# LIDO-HW_100_FrontConnector.net
KiCad netlist of a schematic drawn in Altium Designer
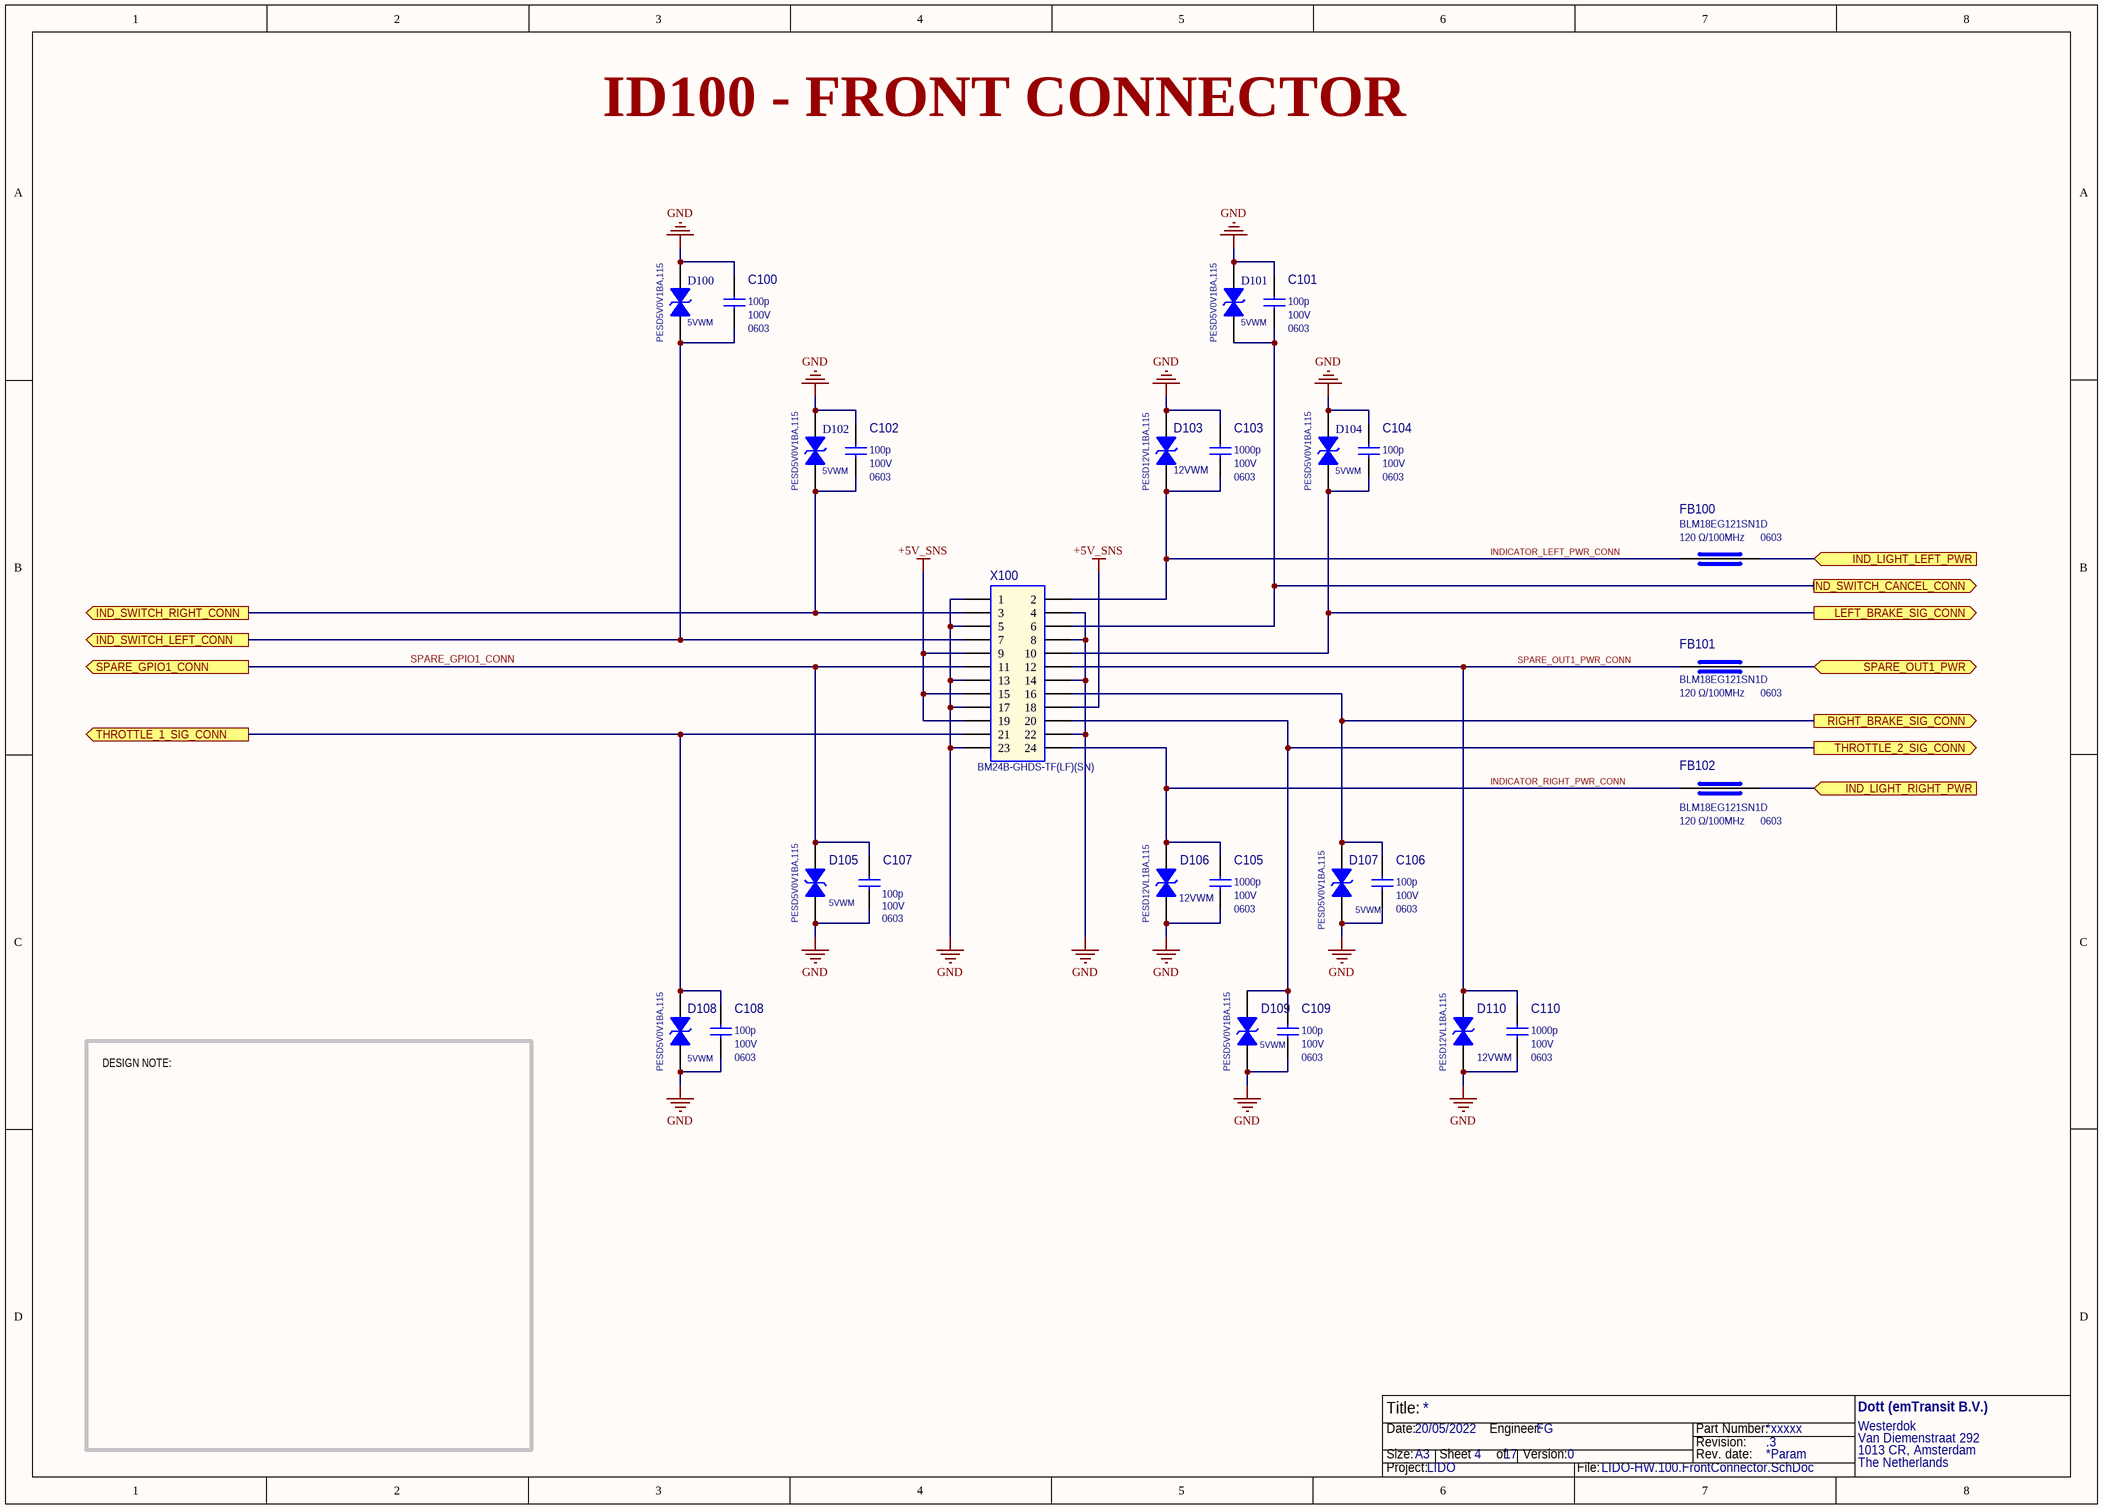
[diagram p0: LIDO-HW.100.FrontConnector.SchDoc]

(export (version "E")
  (design (tool "Eeschema 10.0.6"))
  (components
    (comp (ref "C100")
      (value "100p")
      (footprint "CAP_0603_1608X90-N_MURATA_A")
      (description "CAP CER 100PF 100V C0G 0603")
      (fields
        (field (name "MANUFACTURER PART NUMBER") "CGA3E2C0G2A101J080AA")
        (field (name "MANUFACTURER") "TDK Corporation")
        (field (name "PART VALUE") "100p")
        (field (name "PART VALUE 2") "100V")
        (field (name "PART PACKAGE") "0603")
      )
      (libsource (lib "DB_Library") (part "Ceramic"))
    )
    (comp (ref "C101")
      (value "100p")
      (footprint "CAP_0603_1608X90-N_MURATA_A")
      (description "CAP CER 100PF 100V C0G 0603")
      (fields
        (field (name "MANUFACTURER PART NUMBER") "CGA3E2C0G2A101J080AA")
        (field (name "MANUFACTURER") "TDK Corporation")
        (field (name "PART VALUE") "100p")
        (field (name "PART VALUE 2") "100V")
        (field (name "PART PACKAGE") "0603")
      )
      (libsource (lib "DB_Library") (part "Ceramic"))
    )
    (comp (ref "C102")
      (value "100p")
      (footprint "CAP_0603_1608X90-N_MURATA_A")
      (description "CAP CER 100PF 100V C0G 0603")
      (fields
        (field (name "MANUFACTURER PART NUMBER") "CGA3E2C0G2A101J080AA")
        (field (name "MANUFACTURER") "TDK Corporation")
        (field (name "PART VALUE") "100p")
        (field (name "PART VALUE 2") "100V")
        (field (name "PART PACKAGE") "0603")
      )
      (libsource (lib "DB_Library") (part "Ceramic"))
    )
    (comp (ref "C103")
      (value "1000p")
      (footprint "CAP_0603_1608X90-N_MURATA_A")
      (description "CAP CER 1000PF 100V X7R 0603")
      (fields
        (field (name "MANUFACTURER PART NUMBER") "CGA3E2X7R2A102K080AA")
        (field (name "MANUFACTURER") "TDK Corporation")
        (field (name "PART VALUE") "1000p")
        (field (name "PART VALUE 2") "100V")
        (field (name "PART PACKAGE") "0603")
      )
      (libsource (lib "DB_Library") (part "Ceramic"))
    )
    (comp (ref "C104")
      (value "100p")
      (footprint "CAP_0603_1608X90-N_MURATA_A")
      (description "CAP CER 100PF 100V C0G 0603")
      (fields
        (field (name "MANUFACTURER PART NUMBER") "CGA3E2C0G2A101J080AA")
        (field (name "MANUFACTURER") "TDK Corporation")
        (field (name "PART VALUE") "100p")
        (field (name "PART VALUE 2") "100V")
        (field (name "PART PACKAGE") "0603")
      )
      (libsource (lib "DB_Library") (part "Ceramic"))
    )
    (comp (ref "C105")
      (value "1000p")
      (footprint "CAP_0603_1608X90-N_MURATA_A")
      (description "CAP CER 1000PF 100V X7R 0603")
      (fields
        (field (name "MANUFACTURER PART NUMBER") "CGA3E2X7R2A102K080AA")
        (field (name "MANUFACTURER") "TDK Corporation")
        (field (name "PART VALUE") "1000p")
        (field (name "PART VALUE 2") "100V")
        (field (name "PART PACKAGE") "0603")
      )
      (libsource (lib "DB_Library") (part "Ceramic"))
    )
    (comp (ref "C106")
      (value "100p")
      (footprint "CAP_0603_1608X90-N_MURATA_A")
      (description "CAP CER 100PF 100V C0G 0603")
      (fields
        (field (name "MANUFACTURER PART NUMBER") "CGA3E2C0G2A101J080AA")
        (field (name "MANUFACTURER") "TDK Corporation")
        (field (name "PART VALUE") "100p")
        (field (name "PART VALUE 2") "100V")
        (field (name "PART PACKAGE") "0603")
      )
      (libsource (lib "DB_Library") (part "Ceramic"))
    )
    (comp (ref "C107")
      (value "100p")
      (footprint "CAP_0603_1608X90-N_MURATA_A")
      (description "CAP CER 100PF 100V C0G 0603")
      (fields
        (field (name "MANUFACTURER PART NUMBER") "CGA3E2C0G2A101J080AA")
        (field (name "MANUFACTURER") "TDK Corporation")
        (field (name "PART VALUE") "100p")
        (field (name "PART VALUE 2") "100V")
        (field (name "PART PACKAGE") "0603")
      )
      (libsource (lib "DB_Library") (part "Ceramic"))
    )
    (comp (ref "C108")
      (value "100p")
      (footprint "CAP_0603_1608X90-N_MURATA_A")
      (description "CAP CER 100PF 100V C0G 0603")
      (fields
        (field (name "MANUFACTURER PART NUMBER") "CGA3E2C0G2A101J080AA")
        (field (name "MANUFACTURER") "TDK Corporation")
        (field (name "PART VALUE") "100p")
        (field (name "PART VALUE 2") "100V")
        (field (name "PART PACKAGE") "0603")
      )
      (libsource (lib "DB_Library") (part "Ceramic"))
    )
    (comp (ref "C109")
      (value "100p")
      (footprint "CAP_0603_1608X90-N_MURATA_A")
      (description "CAP CER 100PF 100V C0G 0603")
      (fields
        (field (name "MANUFACTURER PART NUMBER") "CGA3E2C0G2A101J080AA")
        (field (name "MANUFACTURER") "TDK Corporation")
        (field (name "PART VALUE") "100p")
        (field (name "PART VALUE 2") "100V")
        (field (name "PART PACKAGE") "0603")
      )
      (libsource (lib "DB_Library") (part "Ceramic"))
    )
    (comp (ref "C110")
      (value "1000p")
      (footprint "CAP_0603_1608X90-N_MURATA_A")
      (description "CAP CER 1000PF 100V X7R 0603")
      (fields
        (field (name "MANUFACTURER PART NUMBER") "CGA3E2X7R2A102K080AA")
        (field (name "MANUFACTURER") "TDK Corporation")
        (field (name "PART VALUE") "1000p")
        (field (name "PART VALUE 2") "100V")
        (field (name "PART PACKAGE") "0603")
      )
      (libsource (lib "DB_Library") (part "Ceramic"))
    )
    (comp (ref "D100")
      (value "5VWM")
      (footprint "NXP_SOD-323_250X125X95L30x32_A")
      (description "12.5V Clamp 4.8A (8/20µs) Ipp Tvs Diode Surface Mount SOD-323")
      (fields
        (field (name "MANUFACTURER PART NUMBER") "PESD5V0V1BA,115")
        (field (name "MANUFACTURER") "Nexperia USA Inc.")
        (field (name "PART VALUE") "5VWM")
        (field (name "OBSOLETE PART") "False")
      )
      (libsource (lib "DB_Library") (part "BI-TVS_DIODE_B"))
    )
    (comp (ref "D101")
      (value "5VWM")
      (footprint "NXP_SOD-323_250X125X95L30x32_A")
      (description "12.5V Clamp 4.8A (8/20µs) Ipp Tvs Diode Surface Mount SOD-323")
      (fields
        (field (name "MANUFACTURER PART NUMBER") "PESD5V0V1BA,115")
        (field (name "MANUFACTURER") "Nexperia USA Inc.")
        (field (name "PART VALUE") "5VWM")
        (field (name "OBSOLETE PART") "False")
      )
      (libsource (lib "DB_Library") (part "BI-TVS_DIODE_B"))
    )
    (comp (ref "D102")
      (value "5VWM")
      (footprint "NXP_SOD-323_250X125X95L30x32_A")
      (description "12.5V Clamp 4.8A (8/20µs) Ipp Tvs Diode Surface Mount SOD-323")
      (fields
        (field (name "MANUFACTURER PART NUMBER") "PESD5V0V1BA,115")
        (field (name "MANUFACTURER") "Nexperia USA Inc.")
        (field (name "PART VALUE") "5VWM")
        (field (name "OBSOLETE PART") "False")
      )
      (libsource (lib "DB_Library") (part "BI-TVS_DIODE_B"))
    )
    (comp (ref "D103")
      (value "12VWM")
      (footprint "NXP_SOD-323_250X125X95L30x32_A")
      (description "37V Clamp 5A (8/20µs) Ipp Tvs Diode Surface Mount SOD-323")
      (fields
        (field (name "MANUFACTURER PART NUMBER") "PESD12VL1BA,115")
        (field (name "MANUFACTURER") "Nexperia USA Inc.")
        (field (name "PART VALUE") "12VWM")
        (field (name "OBSOLETE PART") "False")
      )
      (libsource (lib "DB_Library") (part "BI-TVS_DIODE_B"))
    )
    (comp (ref "D104")
      (value "5VWM")
      (footprint "NXP_SOD-323_250X125X95L30x32_A")
      (description "12.5V Clamp 4.8A (8/20µs) Ipp Tvs Diode Surface Mount SOD-323")
      (fields
        (field (name "MANUFACTURER PART NUMBER") "PESD5V0V1BA,115")
        (field (name "MANUFACTURER") "Nexperia USA Inc.")
        (field (name "PART VALUE") "5VWM")
        (field (name "OBSOLETE PART") "False")
      )
      (libsource (lib "DB_Library") (part "BI-TVS_DIODE_B"))
    )
    (comp (ref "D105")
      (value "5VWM")
      (footprint "NXP_SOD-323_250X125X95L30x32_A")
      (description "12.5V Clamp 4.8A (8/20µs) Ipp Tvs Diode Surface Mount SOD-323")
      (fields
        (field (name "MANUFACTURER PART NUMBER") "PESD5V0V1BA,115")
        (field (name "MANUFACTURER") "Nexperia USA Inc.")
        (field (name "PART VALUE") "5VWM")
        (field (name "OBSOLETE PART") "False")
      )
      (libsource (lib "DB_Library") (part "BI-TVS_DIODE_B"))
    )
    (comp (ref "D106")
      (value "12VWM")
      (footprint "NXP_SOD-323_250X125X95L30x32_A")
      (description "37V Clamp 5A (8/20µs) Ipp Tvs Diode Surface Mount SOD-323")
      (fields
        (field (name "MANUFACTURER PART NUMBER") "PESD12VL1BA,115")
        (field (name "MANUFACTURER") "Nexperia USA Inc.")
        (field (name "PART VALUE") "12VWM")
        (field (name "OBSOLETE PART") "False")
      )
      (libsource (lib "DB_Library") (part "BI-TVS_DIODE_B"))
    )
    (comp (ref "D107")
      (value "5VWM")
      (footprint "NXP_SOD-323_250X125X95L30x32_A")
      (description "12.5V Clamp 4.8A (8/20µs) Ipp Tvs Diode Surface Mount SOD-323")
      (fields
        (field (name "MANUFACTURER PART NUMBER") "PESD5V0V1BA,115")
        (field (name "MANUFACTURER") "Nexperia USA Inc.")
        (field (name "PART VALUE") "5VWM")
        (field (name "OBSOLETE PART") "False")
      )
      (libsource (lib "DB_Library") (part "BI-TVS_DIODE_B"))
    )
    (comp (ref "D108")
      (value "5VWM")
      (footprint "NXP_SOD-323_250X125X95L30x32_A")
      (description "12.5V Clamp 4.8A (8/20µs) Ipp Tvs Diode Surface Mount SOD-323")
      (fields
        (field (name "MANUFACTURER PART NUMBER") "PESD5V0V1BA,115")
        (field (name "MANUFACTURER") "Nexperia USA Inc.")
        (field (name "PART VALUE") "5VWM")
        (field (name "OBSOLETE PART") "False")
      )
      (libsource (lib "DB_Library") (part "BI-TVS_DIODE_B"))
    )
    (comp (ref "D109")
      (value "5VWM")
      (footprint "NXP_SOD-323_250X125X95L30x32_A")
      (description "12.5V Clamp 4.8A (8/20µs) Ipp Tvs Diode Surface Mount SOD-323")
      (fields
        (field (name "MANUFACTURER PART NUMBER") "PESD5V0V1BA,115")
        (field (name "MANUFACTURER") "Nexperia USA Inc.")
        (field (name "PART VALUE") "5VWM")
        (field (name "OBSOLETE PART") "False")
      )
      (libsource (lib "DB_Library") (part "BI-TVS_DIODE_B"))
    )
    (comp (ref "D110")
      (value "12VWM")
      (footprint "NXP_SOD-323_250X125X95L30x32_A")
      (description "37V Clamp 5A (8/20µs) Ipp Tvs Diode Surface Mount SOD-323")
      (fields
        (field (name "MANUFACTURER PART NUMBER") "PESD12VL1BA,115")
        (field (name "MANUFACTURER") "Nexperia USA Inc.")
        (field (name "PART VALUE") "12VWM")
        (field (name "OBSOLETE PART") "False")
      )
      (libsource (lib "DB_Library") (part "BI-TVS_DIODE_B"))
    )
    (comp (ref "FB100")
      (value "120 Ω/100MHz")
      (footprint "IND_0603_1608X95-N_AVX_A")
      (description "FERRITE BEAD 120 OHM 0603 1LN")
      (fields
        (field (name "MANUFACTURER PART NUMBER") "BLM18EG121SN1D")
        (field (name "MANUFACTURER") "Murata Electronics")
        (field (name "PART VALUE") "120 Ω/100MHz")
        (field (name "PART PACKAGE") "0603")
        (field (name "OBSOLETE PART") "False")
      )
      (libsource (lib "DB_Library") (part "FERRITE_BEAD"))
    )
    (comp (ref "FB101")
      (value "120 Ω/100MHz")
      (footprint "IND_0603_1608X95-N_AVX_A")
      (description "FERRITE BEAD 120 OHM 0603 1LN")
      (fields
        (field (name "MANUFACTURER PART NUMBER") "BLM18EG121SN1D")
        (field (name "MANUFACTURER") "Murata Electronics")
        (field (name "PART VALUE") "120 Ω/100MHz")
        (field (name "PART PACKAGE") "0603")
        (field (name "OBSOLETE PART") "False")
      )
      (libsource (lib "DB_Library") (part "FERRITE_BEAD"))
    )
    (comp (ref "FB102")
      (value "120 Ω/100MHz")
      (footprint "IND_0603_1608X95-N_AVX_A")
      (description "FERRITE BEAD 120 OHM 0603 1LN")
      (fields
        (field (name "MANUFACTURER PART NUMBER") "BLM18EG121SN1D")
        (field (name "MANUFACTURER") "Murata Electronics")
        (field (name "PART VALUE") "120 Ω/100MHz")
        (field (name "PART PACKAGE") "0603")
        (field (name "OBSOLETE PART") "False")
      )
      (libsource (lib "DB_Library") (part "FERRITE_BEAD"))
    )
    (comp (ref "X100")
      (value "BM24B-GHDS-TF(LF)(SN)")
      (footprint "JST_BM24B-GHDS-TF_A")
      (description "Connector Header Surface Mount 24 position 0.049\" (1.25mm)")
      (fields (field (name "MANUFACTURER") "JST Sales America Inc.") (field (name "OBSOLETE PART") "False"))
      (libsource (lib "DB_Library") (part "RECT_24PIN_2R_A"))
    )
  )
  (nets
    (net (code "1") (name "+5V_SNS") (class "Default")
      (node (ref "X100") (pin "15") (pinfunction "15_15") (pintype "passive"))
      (node (ref "X100") (pin "18") (pinfunction "18_18") (pintype "passive"))
      (node (ref "X100") (pin "19") (pinfunction "19_19") (pintype "passive"))
      (node (ref "X100") (pin "9") (pinfunction "9_9") (pintype "passive"))
    )
    (net (code "2") (name "/INDICATOR_LEFT_PWR_CONN") (class "Default")
      (node (ref "C103") (pin "2") (pinfunction "2_2") (pintype "passive"))
      (node (ref "D103") (pin "C") (pinfunction "C_C") (pintype "passive"))
      (node (ref "FB100") (pin "1") (pinfunction "1_1") (pintype "passive"))
      (node (ref "X100") (pin "2") (pinfunction "2_2") (pintype "passive"))
    )
    (net (code "3") (name "/INDICATOR_RIGHT_PWR_CONN") (class "Default")
      (node (ref "C105") (pin "1") (pinfunction "1_1") (pintype "passive"))
      (node (ref "D106") (pin "C") (pinfunction "C_C") (pintype "passive"))
      (node (ref "FB102") (pin "1") (pinfunction "1_1") (pintype "passive"))
      (node (ref "X100") (pin "24") (pinfunction "24_24") (pintype "passive"))
    )
    (net (code "4") (name "/IND_LIGHT_LEFT_PWR") (class "Default")
      (node (ref "FB100") (pin "2") (pinfunction "2_2") (pintype "passive"))
    )
    (net (code "5") (name "/IND_LIGHT_RIGHT_PWR") (class "Default")
      (node (ref "FB102") (pin "2") (pinfunction "2_2") (pintype "passive"))
    )
    (net (code "6") (name "/IND_SWITCH_CANCEL_CONN") (class "Default")
      (node (ref "C101") (pin "2") (pinfunction "2_2") (pintype "passive"))
      (node (ref "D101") (pin "C") (pinfunction "C_C") (pintype "passive"))
      (node (ref "X100") (pin "6") (pinfunction "6_6") (pintype "passive"))
    )
    (net (code "7") (name "/IND_SWITCH_LEFT_CONN") (class "Default")
      (node (ref "C100") (pin "2") (pinfunction "2_2") (pintype "passive"))
      (node (ref "D100") (pin "C") (pinfunction "C_C") (pintype "passive"))
      (node (ref "X100") (pin "7") (pinfunction "7_7") (pintype "passive"))
    )
    (net (code "8") (name "/IND_SWITCH_RIGHT_CONN") (class "Default")
      (node (ref "C102") (pin "2") (pinfunction "2_2") (pintype "passive"))
      (node (ref "D102") (pin "C") (pinfunction "C_C") (pintype "passive"))
      (node (ref "X100") (pin "3") (pinfunction "3_3") (pintype "passive"))
    )
    (net (code "9") (name "/LEFT_BRAKE_SIG_CONN") (class "Default")
      (node (ref "C104") (pin "2") (pinfunction "2_2") (pintype "passive"))
      (node (ref "D104") (pin "C") (pinfunction "C_C") (pintype "passive"))
      (node (ref "X100") (pin "10") (pinfunction "10_10") (pintype "passive"))
    )
    (net (code "10") (name "/RIGHT_BRAKE_SIG_CONN") (class "Default")
      (node (ref "C106") (pin "1") (pinfunction "1_1") (pintype "passive"))
      (node (ref "D107") (pin "C") (pinfunction "C_C") (pintype "passive"))
      (node (ref "X100") (pin "16") (pinfunction "16_16") (pintype "passive"))
    )
    (net (code "11") (name "/SPARE_GPIO1_CONN") (class "Default")
      (node (ref "C107") (pin "2") (pinfunction "2_2") (pintype "passive"))
      (node (ref "D105") (pin "C") (pinfunction "C_C") (pintype "passive"))
      (node (ref "X100") (pin "11") (pinfunction "11_11") (pintype "passive"))
    )
    (net (code "12") (name "/SPARE_OUT1_PWR") (class "Default")
      (node (ref "FB101") (pin "1") (pinfunction "1_1") (pintype "passive"))
    )
    (net (code "13") (name "/SPARE_OUT1_PWR_CONN") (class "Default")
      (node (ref "C110") (pin "1") (pinfunction "1_1") (pintype "passive"))
      (node (ref "D110") (pin "C") (pinfunction "C_C") (pintype "passive"))
      (node (ref "FB101") (pin "2") (pinfunction "2_2") (pintype "passive"))
      (node (ref "X100") (pin "12") (pinfunction "12_12") (pintype "passive"))
    )
    (net (code "14") (name "/THROTTLE_1_SIG_CONN") (class "Default")
      (node (ref "C108") (pin "1") (pinfunction "1_1") (pintype "passive"))
      (node (ref "D108") (pin "C") (pinfunction "C_C") (pintype "passive"))
      (node (ref "X100") (pin "21") (pinfunction "21_21") (pintype "passive"))
    )
    (net (code "15") (name "/THROTTLE_2_SIG_CONN") (class "Default")
      (node (ref "C109") (pin "1") (pinfunction "1_1") (pintype "passive"))
      (node (ref "D109") (pin "C") (pinfunction "C_C") (pintype "passive"))
      (node (ref "X100") (pin "20") (pinfunction "20_20") (pintype "passive"))
    )
    (net (code "16") (name "GND") (class "Default")
      (node (ref "C100") (pin "1") (pinfunction "1_1") (pintype "passive"))
      (node (ref "C101") (pin "1") (pinfunction "1_1") (pintype "passive"))
      (node (ref "C102") (pin "1") (pinfunction "1_1") (pintype "passive"))
      (node (ref "C103") (pin "1") (pinfunction "1_1") (pintype "passive"))
      (node (ref "C104") (pin "1") (pinfunction "1_1") (pintype "passive"))
      (node (ref "C105") (pin "2") (pinfunction "2_2") (pintype "passive"))
      (node (ref "C106") (pin "2") (pinfunction "2_2") (pintype "passive"))
      (node (ref "C107") (pin "1") (pinfunction "1_1") (pintype "passive"))
      (node (ref "C108") (pin "2") (pinfunction "2_2") (pintype "passive"))
      (node (ref "C109") (pin "2") (pinfunction "2_2") (pintype "passive"))
      (node (ref "C110") (pin "2") (pinfunction "2_2") (pintype "passive"))
      (node (ref "D100") (pin "A") (pinfunction "A_A") (pintype "passive"))
      (node (ref "D101") (pin "A") (pinfunction "A_A") (pintype "passive"))
      (node (ref "D102") (pin "A") (pinfunction "A_A") (pintype "passive"))
      (node (ref "D103") (pin "A") (pinfunction "A_A") (pintype "passive"))
      (node (ref "D104") (pin "A") (pinfunction "A_A") (pintype "passive"))
      (node (ref "D105") (pin "A") (pinfunction "A_A") (pintype "passive"))
      (node (ref "D106") (pin "A") (pinfunction "A_A") (pintype "passive"))
      (node (ref "D107") (pin "A") (pinfunction "A_A") (pintype "passive"))
      (node (ref "D108") (pin "A") (pinfunction "A_A") (pintype "passive"))
      (node (ref "D109") (pin "A") (pinfunction "A_A") (pintype "passive"))
      (node (ref "D110") (pin "A") (pinfunction "A_A") (pintype "passive"))
      (node (ref "X100") (pin "1") (pinfunction "1_1") (pintype "passive"))
      (node (ref "X100") (pin "13") (pinfunction "13_13") (pintype "passive"))
      (node (ref "X100") (pin "14") (pinfunction "14_14") (pintype "passive"))
      (node (ref "X100") (pin "17") (pinfunction "17_17") (pintype "passive"))
      (node (ref "X100") (pin "22") (pinfunction "22_22") (pintype "passive"))
      (node (ref "X100") (pin "23") (pinfunction "23_23") (pintype "passive"))
      (node (ref "X100") (pin "4") (pinfunction "4_4") (pintype "passive"))
      (node (ref "X100") (pin "5") (pinfunction "5_5") (pintype "passive"))
      (node (ref "X100") (pin "8") (pinfunction "8_8") (pintype "passive"))
    )
  )
)
